# SCH_Victron-Orion-DC-DC-Charger-Cooling-.net
KiCad netlist of a schematic drawn in EasyEDA
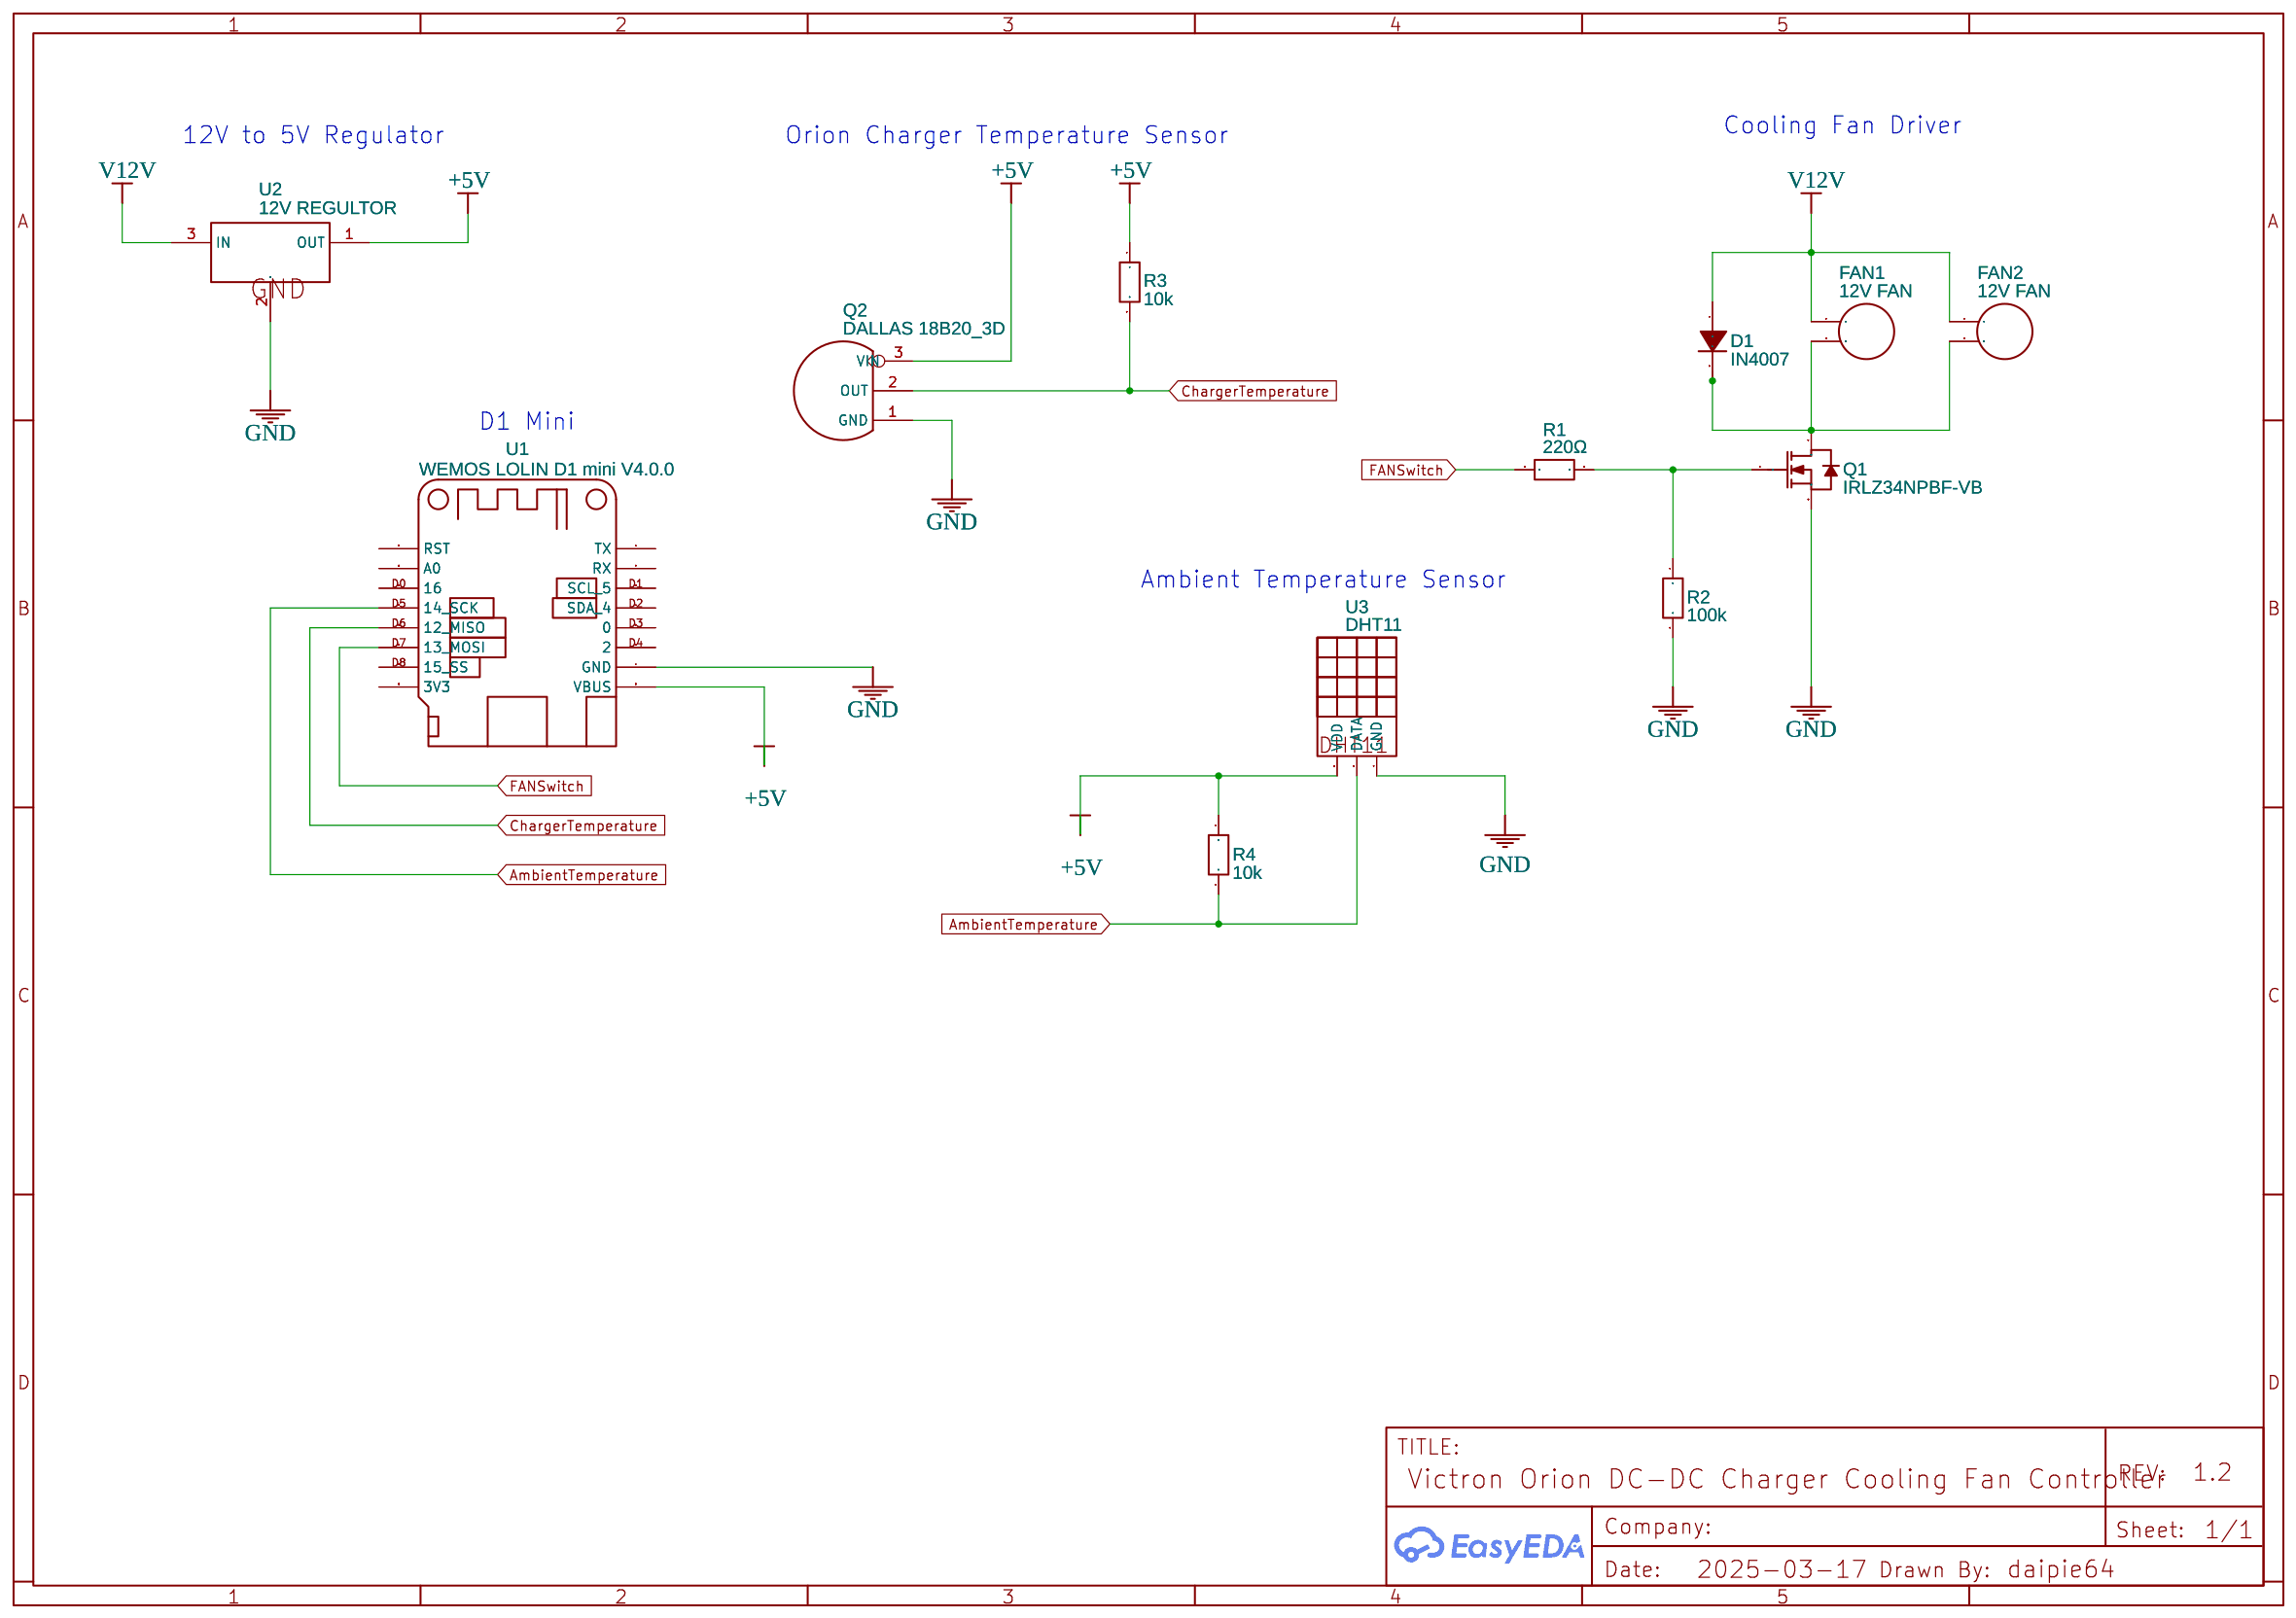
[diagram p0: schematic sheet]

(export (version "E")
  (design (tool "Eeschema 10.0.6"))
  (components
    (comp (ref "D1")
      (value "IN4007")
      (fields (field (name "Manufacturer Part") "1N4007") (field (name "Manufacturer") "ST(先科)"))
      (libsource (lib "") (part "1N4007"))
    )
    (comp (ref "FAN1") (value "12V FAN") (libsource (lib "") (part "FAN COPY")))
    (comp (ref "FAN2") (value "12V FAN") (libsource (lib "") (part "FAN COPY")))
    (comp (ref "Q1")
      (value "IRLZ34NPBF-VB")
      (fields (field (name "Manufacturer") "VBsemi(微碧半导体)"))
      (libsource (lib "") (part "IRLZ34NPBF-VB"))
    )
    (comp (ref "Q2")
      (value "DALLAS 18B20_3D")
      (fields (field (name "Manufacturer Part") "DS18B20"))
      (libsource (lib "") (part "DALLAS 18B20_3D"))
    )
    (comp (ref "R1") (value "220Ω") (libsource (lib "") (part "R_0603_EU_1")))
    (comp (ref "R2") (value "100k") (libsource (lib "") (part "R_0603_EU")))
    (comp (ref "R3") (value "10k") (libsource (lib "") (part "R_0603_EU")))
    (comp (ref "R4") (value "10k") (libsource (lib "") (part "R_0603_EU")))
    (comp (ref "U1")
      (value "WEMOS LOLIN D1 mini V4.0.0")
      (libsource (lib "") (part "WEMOS LOLIN D1 mini V4.0.0"))
    )
    (comp (ref "U2")
      (value "12V REGULTOR")
      (fields (field (name "Manufacturer Part") "CJ78L05") (field (name "Manufacturer") "CJ"))
      (libsource (lib "") (part "7805(SOT-89)"))
    )
    (comp (ref "U3") (value "DHT11") (libsource (lib "") (part "DHT11")))
  )
  (nets
    (net (code "1") (name "+5V") (class "Default")
      (node (ref "Q2") (pin "3") (pinfunction "VIN_3") (pintype "unspecified"))
      (node (ref "R3") (pin "1") (pinfunction "1_1") (pintype "unspecified"))
      (node (ref "R4") (pin "1") (pinfunction "1_1") (pintype "unspecified"))
      (node (ref "U1") (pin "8") (pinfunction "VBUS_8") (pintype "unspecified"))
      (node (ref "U2") (pin "1") (pinfunction "OUT_1") (pintype "passive"))
      (node (ref "U3") (pin "3") (pinfunction "VDD_3") (pintype "unspecified"))
    )
    (net (code "2") (name "AmbientTemperature") (class "Default")
      (node (ref "R4") (pin "2") (pinfunction "2_2") (pintype "unspecified"))
      (node (ref "U1") (pin "12") (pinfunction "14_SCK_12") (pintype "unspecified"))
      (node (ref "U3") (pin "2") (pinfunction "DATA_2") (pintype "unspecified"))
    )
    (net (code "3") (name "ChargerTemperature") (class "Default")
      (node (ref "Q2") (pin "2") (pinfunction "OUT_2") (pintype "unspecified"))
      (node (ref "R3") (pin "2") (pinfunction "2_2") (pintype "unspecified"))
      (node (ref "U1") (pin "13") (pinfunction "12_MISO_13") (pintype "unspecified"))
    )
    (net (code "4") (name "FANSwitch") (class "Default")
      (node (ref "R1") (pin "1") (pinfunction "1_1") (pintype "unspecified"))
      (node (ref "U1") (pin "14") (pinfunction "13_MOSI_14") (pintype "unspecified"))
    )
    (net (code "5") (name "GND") (class "Default")
      (node (ref "Q1") (pin "3") (pinfunction "S_3") (pintype "unspecified"))
      (node (ref "Q2") (pin "1") (pinfunction "GND_1") (pintype "unspecified"))
      (node (ref "R2") (pin "2") (pinfunction "2_2") (pintype "unspecified"))
      (node (ref "U1") (pin "7") (pinfunction "GND_7") (pintype "unspecified"))
      (node (ref "U2") (pin "2") (pinfunction "GND_2") (pintype "passive"))
      (node (ref "U3") (pin "1") (pinfunction "GND_1") (pintype "unspecified"))
    )
    (net (code "6") (name "Net-(D1-K)") (class "Default")
      (node (ref "D1") (pin "2") (pinfunction "K_2") (pintype "unspecified"))
      (node (ref "FAN1") (pin "2") (pinfunction "2_2") (pintype "unspecified"))
      (node (ref "FAN2") (pin "2") (pinfunction "2_2") (pintype "unspecified"))
      (node (ref "Q1") (pin "2") (pinfunction "D_2") (pintype "unspecified"))
    )
    (net (code "7") (name "Net-(Q1-G)") (class "Default")
      (node (ref "Q1") (pin "1") (pinfunction "G_1") (pintype "unspecified"))
      (node (ref "R1") (pin "2") (pinfunction "2_2") (pintype "unspecified"))
      (node (ref "R2") (pin "1") (pinfunction "1_1") (pintype "unspecified"))
    )
    (net (code "8") (name "V12V") (class "Default")
      (node (ref "D1") (pin "1") (pinfunction "A_1") (pintype "unspecified"))
      (node (ref "FAN1") (pin "1") (pinfunction "1_1") (pintype "unspecified"))
      (node (ref "FAN2") (pin "1") (pinfunction "1_1") (pintype "unspecified"))
      (node (ref "U2") (pin "3") (pinfunction "IN_3") (pintype "passive"))
    )
    (net (code "9") (name "unconnected-(U1-0-Pad5)") (class "Default")
      (node (ref "U1") (pin "5") (pinfunction "0_5") (pintype "unspecified"))
    )
    (net (code "10") (name "unconnected-(U1-2-Pad6)") (class "Default")
      (node (ref "U1") (pin "6") (pinfunction "2_6") (pintype "unspecified"))
    )
    (net (code "11") (name "unconnected-(U1-3V3-Pad16)") (class "Default")
      (node (ref "U1") (pin "16") (pinfunction "3V3_16") (pintype "unspecified"))
    )
    (net (code "12") (name "unconnected-(U1-15_SS-Pad15)") (class "Default")
      (node (ref "U1") (pin "15") (pinfunction "15_SS_15") (pintype "unspecified"))
    )
    (net (code "13") (name "unconnected-(U1-16-Pad11)") (class "Default")
      (node (ref "U1") (pin "11") (pinfunction "16_11") (pintype "unspecified"))
    )
    (net (code "14") (name "unconnected-(U1-A0-Pad10)") (class "Default")
      (node (ref "U1") (pin "10") (pinfunction "A0_10") (pintype "unspecified"))
    )
    (net (code "15") (name "unconnected-(U1-RST-Pad9)") (class "Default")
      (node (ref "U1") (pin "9") (pinfunction "RST_9") (pintype "unspecified"))
    )
    (net (code "16") (name "unconnected-(U1-RX-Pad2)") (class "Default")
      (node (ref "U1") (pin "2") (pinfunction "RX_2") (pintype "unspecified"))
    )
    (net (code "17") (name "unconnected-(U1-SCL_5-Pad3)") (class "Default")
      (node (ref "U1") (pin "3") (pinfunction "SCL_5_3") (pintype "unspecified"))
    )
    (net (code "18") (name "unconnected-(U1-SDA_4-Pad4)") (class "Default")
      (node (ref "U1") (pin "4") (pinfunction "SDA_4_4") (pintype "unspecified"))
    )
    (net (code "19") (name "unconnected-(U1-TX-Pad1)") (class "Default")
      (node (ref "U1") (pin "1") (pinfunction "TX_1") (pintype "unspecified"))
    )
  )
)
